# main_board.net
KiCad netlist of a schematic drawn in EAGLE
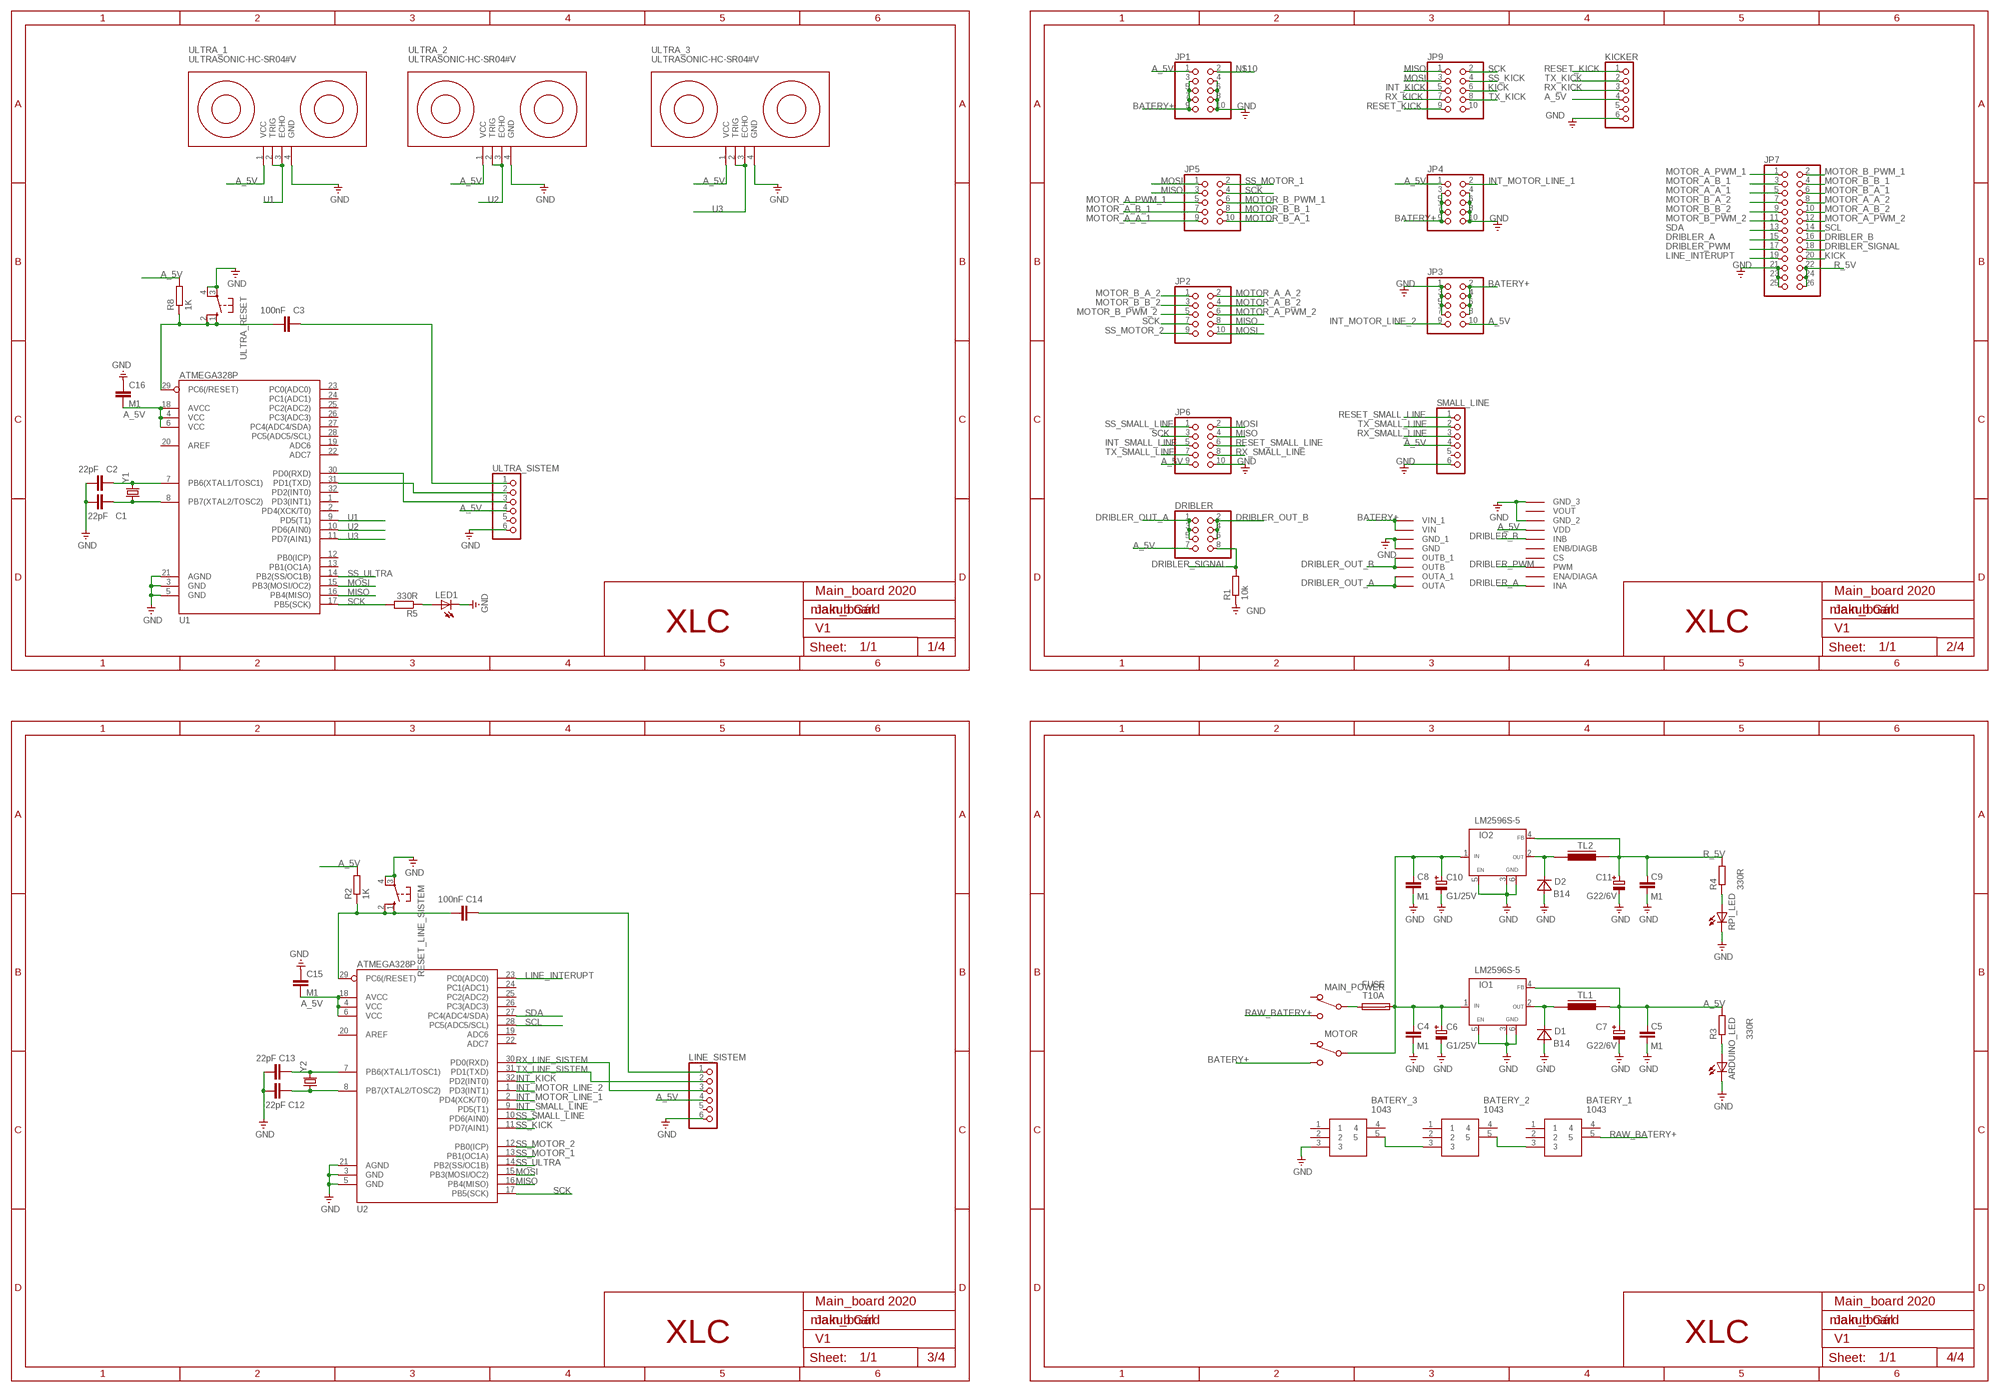
[diagram p0: schematic, sheet 1]

(export (version "E")
  (design (tool "Eeschema 10.0.6"))
  (components
    (comp (ref "ARDUINO_LED")
      (value "LEDCHIPLED_0603")
      (footprint "eagle-import:CHIPLED_0603")
      (libsource (lib "eagle-import") (part "LEDCHIPLED_0603"))
    )
    (comp (ref "BATERY_1")
      (value "1043")
      (footprint "eagle-import:1043")
      (fields (field (name "MOUSER_PART_NUMBER") "534-1043"))
      (libsource (lib "eagle-import") (part "1043"))
    )
    (comp (ref "BATERY_2")
      (value "1043")
      (footprint "eagle-import:1043")
      (fields (field (name "MOUSER_PART_NUMBER") "534-1043"))
      (libsource (lib "eagle-import") (part "1043"))
    )
    (comp (ref "BATERY_3")
      (value "1043")
      (footprint "eagle-import:1043")
      (fields (field (name "MOUSER_PART_NUMBER") "534-1043"))
      (libsource (lib "eagle-import") (part "1043"))
    )
    (comp (ref "C1")
      (value "22pF")
      (footprint "eagle-import:C0603")
      (libsource (lib "eagle-import") (part "C-EUC0603"))
    )
    (comp (ref "C2")
      (value "22pF")
      (footprint "eagle-import:C0603")
      (libsource (lib "eagle-import") (part "C-EUC0603"))
    )
    (comp (ref "C3")
      (value "100nF")
      (footprint "eagle-import:C0603")
      (libsource (lib "eagle-import") (part "C-EUC0603"))
    )
    (comp (ref "C4")
      (value "M1")
      (footprint "eagle-import:SMD-1206")
      (libsource (lib "eagle-import") (part "KOND-KERAM1206-SMD"))
    )
    (comp (ref "C5")
      (value "M1")
      (footprint "eagle-import:SMD-1206")
      (libsource (lib "eagle-import") (part "KOND-KERAM1206-SMD"))
    )
    (comp (ref "C6")
      (value "G1/25V")
      (footprint "eagle-import:SMD-ELE-D")
      (libsource (lib "eagle-import") (part "KOND-ELEKTD-SMD"))
    )
    (comp (ref "C7")
      (value "G22/6V")
      (footprint "eagle-import:SMD-ELE-D")
      (libsource (lib "eagle-import") (part "KOND-ELEKTD-SMD"))
    )
    (comp (ref "C8")
      (value "M1")
      (footprint "eagle-import:SMD-1206")
      (libsource (lib "eagle-import") (part "KOND-KERAM1206-SMD"))
    )
    (comp (ref "C9")
      (value "M1")
      (footprint "eagle-import:SMD-1206")
      (libsource (lib "eagle-import") (part "KOND-KERAM1206-SMD"))
    )
    (comp (ref "C10")
      (value "G1/25V")
      (footprint "eagle-import:SMD-ELE-D")
      (libsource (lib "eagle-import") (part "KOND-ELEKTD-SMD"))
    )
    (comp (ref "C11")
      (value "G22/6V")
      (footprint "eagle-import:SMD-ELE-D")
      (libsource (lib "eagle-import") (part "KOND-ELEKTD-SMD"))
    )
    (comp (ref "C12")
      (value "22pF")
      (footprint "eagle-import:C0603")
      (libsource (lib "eagle-import") (part "C-EUC0603"))
    )
    (comp (ref "C13")
      (value "22pF")
      (footprint "eagle-import:C0603")
      (libsource (lib "eagle-import") (part "C-EUC0603"))
    )
    (comp (ref "C14")
      (value "100nF")
      (footprint "eagle-import:C0603")
      (libsource (lib "eagle-import") (part "C-EUC0603"))
    )
    (comp (ref "C15")
      (value "M1")
      (footprint "eagle-import:C0603")
      (libsource (lib "eagle-import") (part "rcl_334_C-EUC0603"))
    )
    (comp (ref "C16")
      (value "M1")
      (footprint "eagle-import:C0603")
      (libsource (lib "eagle-import") (part "rcl_334_C-EUC0603"))
    )
    (comp (ref "D1")
      (value "B14")
      (footprint "eagle-import:D-3,6X5,5")
      (libsource (lib "eagle-import") (part "DIODASMD-3,6X5,5"))
    )
    (comp (ref "D2")
      (value "B14")
      (footprint "eagle-import:D-3,6X5,5")
      (libsource (lib "eagle-import") (part "DIODASMD-3,6X5,5"))
    )
    (comp (ref "DRIBLER")
      (value "PINHD-2X4_2.54-SMD")
      (footprint "eagle-import:2X04SMD")
      (libsource (lib "eagle-import") (part "PINHD-2X4_2.54-SMD"))
    )
    (comp (ref "FUSE")
      (value "T10A")
      (footprint "eagle-import:SH22,5A")
      (libsource (lib "eagle-import") (part "POISTKA2A"))
    )
    (comp (ref "IO1")
      (value "LM2596S-5")
      (footprint "eagle-import:TO263-5")
      (libsource (lib "eagle-import") (part "LM2596S"))
    )
    (comp (ref "IO2")
      (value "LM2596S-5")
      (footprint "eagle-import:TO263-5")
      (libsource (lib "eagle-import") (part "LM2596S"))
    )
    (comp (ref "JP1")
      (value "PINHD-2X5IDC")
      (footprint "eagle-import:2X05_IDC")
      (libsource (lib "eagle-import") (part "PINHD-2X5IDC"))
    )
    (comp (ref "JP2")
      (value "PINHD-2X5IDC")
      (footprint "eagle-import:2X05_IDC")
      (libsource (lib "eagle-import") (part "PINHD-2X5IDC"))
    )
    (comp (ref "JP3")
      (value "PINHD-2X5IDC")
      (footprint "eagle-import:2X05_IDC")
      (libsource (lib "eagle-import") (part "PINHD-2X5IDC"))
    )
    (comp (ref "JP4")
      (value "PINHD-2X5IDC")
      (footprint "eagle-import:2X05_IDC")
      (libsource (lib "eagle-import") (part "PINHD-2X5IDC"))
    )
    (comp (ref "JP5")
      (value "PINHD-2X5IDC")
      (footprint "eagle-import:2X05_IDC")
      (libsource (lib "eagle-import") (part "PINHD-2X5IDC"))
    )
    (comp (ref "JP6")
      (value "PINHD-2X5IDC")
      (footprint "eagle-import:2X05_IDC")
      (libsource (lib "eagle-import") (part "PINHD-2X5IDC"))
    )
    (comp (ref "JP7")
      (value "PINHD-2X13_2.54")
      (footprint "eagle-import:2X13")
      (libsource (lib "eagle-import") (part "PINHD-2X13_2.54"))
    )
    (comp (ref "JP9")
      (value "PINHD-2X5IDC")
      (footprint "eagle-import:2X05_IDC")
      (libsource (lib "eagle-import") (part "PINHD-2X5IDC"))
    )
    (comp (ref "KICKER")
      (value "PINHD-1X6")
      (footprint "eagle-import:1X06")
      (libsource (lib "eagle-import") (part "PINHD-1X6"))
    )
    (comp (ref "LED1")
      (value "LEDCHIPLED_0603")
      (footprint "eagle-import:CHIPLED_0603")
      (libsource (lib "eagle-import") (part "LEDCHIPLED_0603"))
    )
    (comp (ref "LINE_SISTEM")
      (value "PINHD-1X6")
      (footprint "eagle-import:1X06")
      (libsource (lib "eagle-import") (part "PINHD-1X6"))
    )
    (comp (ref "MAIN_POWER")
      (value "PREP-1PB")
      (footprint "eagle-import:P-B069B")
      (libsource (lib "eagle-import") (part "PREP-1PB"))
    )
    (comp (ref "MOTOR")
      (value "PREP-1PB")
      (footprint "eagle-import:P-B069B")
      (libsource (lib "eagle-import") (part "PREP-1PB"))
    )
    (comp (ref "R1")
      (value "10k")
      (footprint "eagle-import:R0603")
      (libsource (lib "eagle-import") (part "R-EU_R0603"))
    )
    (comp (ref "R2")
      (value "1K")
      (footprint "eagle-import:R0603")
      (libsource (lib "eagle-import") (part "R-EU_R0603"))
    )
    (comp (ref "R3")
      (value "330R")
      (footprint "eagle-import:R0603")
      (libsource (lib "eagle-import") (part "R-EU_R0603"))
    )
    (comp (ref "R4")
      (value "330R")
      (footprint "eagle-import:R0603")
      (libsource (lib "eagle-import") (part "R-EU_R0603"))
    )
    (comp (ref "R5")
      (value "330R")
      (footprint "eagle-import:R0603")
      (libsource (lib "eagle-import") (part "R-EU_R0603"))
    )
    (comp (ref "R8")
      (value "1K")
      (footprint "eagle-import:R0603")
      (libsource (lib "eagle-import") (part "R-EU_R0603"))
    )
    (comp (ref "RESET_LINE_SISTEM")
      (value "10-XX")
      (footprint "eagle-import:B3F-10XX")
      (fields (field (name "MPN") "B3F-1000"))
      (libsource (lib "eagle-import") (part "10-XX"))
    )
    (comp (ref "RPI_LED")
      (value "LEDCHIPLED_0603")
      (footprint "eagle-import:CHIPLED_0603")
      (libsource (lib "eagle-import") (part "LEDCHIPLED_0603"))
    )
    (comp (ref "SMALL_LINE")
      (value "PINHD-1X6")
      (footprint "eagle-import:1X06")
      (libsource (lib "eagle-import") (part "PINHD-1X6"))
    )
    (comp (ref "TL1")
      (value "INDUK-TLSMD1")
      (footprint "eagle-import:INDUK-TL")
      (libsource (lib "eagle-import") (part "INDUK-TLSMD1"))
    )
    (comp (ref "TL2")
      (value "INDUK-TLSMD1")
      (footprint "eagle-import:INDUK-TL")
      (libsource (lib "eagle-import") (part "INDUK-TLSMD1"))
    )
    (comp (ref "U$4")
      (value "MOTOR_DRIVER")
      (footprint "eagle-import:MOTOR_DRIVER")
      (libsource (lib "eagle-import") (part "MOTOR_DRIVER"))
    )
    (comp (ref "U1")
      (value "ATMEGA328P")
      (footprint "eagle-import:TQFP32-08")
      (libsource (lib "eagle-import") (part "ATMEGA328_SMT"))
    )
    (comp (ref "U2")
      (value "ATMEGA328P")
      (footprint "eagle-import:TQFP32-08")
      (libsource (lib "eagle-import") (part "ATMEGA328_SMT"))
    )
    (comp (ref "ULTRA_1")
      (value "ULTRASONIC-HC-SR04#V")
      (footprint "eagle-import:ULTRASONIC-HC-SR04#V")
      (libsource (lib "eagle-import") (part "ULTRASONIC-HC-SR04#V"))
    )
    (comp (ref "ULTRA_2")
      (value "ULTRASONIC-HC-SR04#V")
      (footprint "eagle-import:ULTRASONIC-HC-SR04#V")
      (libsource (lib "eagle-import") (part "ULTRASONIC-HC-SR04#V"))
    )
    (comp (ref "ULTRA_3")
      (value "ULTRASONIC-HC-SR04#V")
      (footprint "eagle-import:ULTRASONIC-HC-SR04#V")
      (libsource (lib "eagle-import") (part "ULTRASONIC-HC-SR04#V"))
    )
    (comp (ref "ULTRA_RESET")
      (value "10-XX")
      (footprint "eagle-import:B3F-10XX")
      (fields (field (name "MPN") "B3F-1000"))
      (libsource (lib "eagle-import") (part "10-XX"))
    )
    (comp (ref "ULTRA_SISTEM")
      (value "PINHD-1X6")
      (footprint "eagle-import:1X06")
      (libsource (lib "eagle-import") (part "PINHD-1X6"))
    )
    (comp (ref "Y1")
      (value "CRYSTALHC49US")
      (footprint "eagle-import:HC49US")
      (libsource (lib "eagle-import") (part "CRYSTALHC49US"))
    )
    (comp (ref "Y2")
      (value "CRYSTALHC49US")
      (footprint "eagle-import:HC49US")
      (libsource (lib "eagle-import") (part "CRYSTALHC49US"))
    )
  )
  (nets
    (net (code "1") (name "/A_5V") (class "Default")
      (node (ref "C15") (pin "2") (pinfunction "2_2") (pintype "passive"))
      (node (ref "C16") (pin "2") (pinfunction "2_2") (pintype "passive"))
      (node (ref "C5") (pin "2") (pinfunction "2_2") (pintype "passive"))
      (node (ref "C7") (pin "PLUS") (pinfunction "PLUS_PLUS") (pintype "passive"))
      (node (ref "DRIBLER") (pin "7") (pinfunction "7_7") (pintype "passive"))
      (node (ref "IO1") (pin "4") (pinfunction "FB_4") (pintype "input"))
      (node (ref "JP1") (pin "1") (pinfunction "1_1") (pintype "passive"))
      (node (ref "JP3") (pin "10") (pinfunction "10_10") (pintype "passive"))
      (node (ref "JP4") (pin "1") (pinfunction "1_1") (pintype "passive"))
      (node (ref "JP6") (pin "9") (pinfunction "9_9") (pintype "passive"))
      (node (ref "KICKER") (pin "4") (pinfunction "4_4") (pintype "passive"))
      (node (ref "LINE_SISTEM") (pin "4") (pinfunction "4_4") (pintype "passive"))
      (node (ref "R2") (pin "2") (pinfunction "2_2") (pintype "passive"))
      (node (ref "R3") (pin "2") (pinfunction "2_2") (pintype "passive"))
      (node (ref "R8") (pin "2") (pinfunction "2_2") (pintype "passive"))
      (node (ref "SMALL_LINE") (pin "4") (pinfunction "4_4") (pintype "passive"))
      (node (ref "TL1") (pin "2") (pinfunction "2_2") (pintype "passive"))
      (node (ref "U$4") (pin "VDD") (pinfunction "VDD_VDD") (pintype "bidirectional"))
      (node (ref "U1") (pin "18") (pinfunction "AVCC_18") (pintype "bidirectional"))
      (node (ref "U1") (pin "4") (pinfunction "VCC_4") (pintype "bidirectional"))
      (node (ref "U1") (pin "6") (pinfunction "VCC_6") (pintype "bidirectional"))
      (node (ref "U2") (pin "18") (pinfunction "AVCC_18") (pintype "bidirectional"))
      (node (ref "U2") (pin "4") (pinfunction "VCC_4") (pintype "bidirectional"))
      (node (ref "U2") (pin "6") (pinfunction "VCC_6") (pintype "bidirectional"))
      (node (ref "ULTRA_1") (pin "1") (pinfunction "VCC_1") (pintype "power_in"))
      (node (ref "ULTRA_2") (pin "1") (pinfunction "VCC_1") (pintype "power_in"))
      (node (ref "ULTRA_3") (pin "1") (pinfunction "VCC_1") (pintype "power_in"))
      (node (ref "ULTRA_SISTEM") (pin "4") (pinfunction "4_4") (pintype "passive"))
    )
    (net (code "2") (name "/BATERY+") (class "Default")
      (node (ref "JP1") (pin "3") (pinfunction "3_3") (pintype "passive"))
      (node (ref "JP1") (pin "5") (pinfunction "5_5") (pintype "passive"))
      (node (ref "JP1") (pin "7") (pinfunction "7_7") (pintype "passive"))
      (node (ref "JP1") (pin "9") (pinfunction "9_9") (pintype "passive"))
      (node (ref "JP3") (pin "2") (pinfunction "2_2") (pintype "passive"))
      (node (ref "JP3") (pin "4") (pinfunction "4_4") (pintype "passive"))
      (node (ref "JP3") (pin "6") (pinfunction "6_6") (pintype "passive"))
      (node (ref "JP3") (pin "8") (pinfunction "8_8") (pintype "passive"))
      (node (ref "JP4") (pin "3") (pinfunction "3_3") (pintype "passive"))
      (node (ref "JP4") (pin "5") (pinfunction "5_5") (pintype "passive"))
      (node (ref "JP4") (pin "7") (pinfunction "7_7") (pintype "passive"))
      (node (ref "JP4") (pin "9") (pinfunction "9_9") (pintype "passive"))
      (node (ref "MOTOR") (pin "1") (pinfunction "1-OFF_1") (pintype "passive"))
      (node (ref "U$4") (pin "VIN") (pinfunction "VIN_VIN") (pintype "bidirectional"))
      (node (ref "U$4") (pin "VIN_1") (pinfunction "VIN_1_VIN_1") (pintype "bidirectional"))
    )
    (net (code "3") (name "/DRIBLER_A") (class "Default")
      (node (ref "JP7") (pin "15") (pinfunction "15_15") (pintype "passive"))
      (node (ref "U$4") (pin "INA") (pinfunction "INA_INA") (pintype "bidirectional"))
    )
    (net (code "4") (name "/DRIBLER_B") (class "Default")
      (node (ref "JP7") (pin "16") (pinfunction "16_16") (pintype "passive"))
      (node (ref "U$4") (pin "INB") (pinfunction "INB_INB") (pintype "bidirectional"))
    )
    (net (code "5") (name "/DRIBLER_OUT_A") (class "Default")
      (node (ref "DRIBLER") (pin "1") (pinfunction "1_1") (pintype "passive"))
      (node (ref "DRIBLER") (pin "3") (pinfunction "3_3") (pintype "passive"))
      (node (ref "DRIBLER") (pin "5") (pinfunction "5_5") (pintype "passive"))
      (node (ref "U$4") (pin "OUTA") (pinfunction "OUTA_OUTA") (pintype "bidirectional"))
      (node (ref "U$4") (pin "OUTA_1") (pinfunction "OUTA_1_OUTA_1") (pintype "bidirectional"))
    )
    (net (code "6") (name "/DRIBLER_OUT_B") (class "Default")
      (node (ref "DRIBLER") (pin "2") (pinfunction "2_2") (pintype "passive"))
      (node (ref "DRIBLER") (pin "4") (pinfunction "4_4") (pintype "passive"))
      (node (ref "DRIBLER") (pin "6") (pinfunction "6_6") (pintype "passive"))
      (node (ref "U$4") (pin "OUTB") (pinfunction "OUTB_OUTB") (pintype "bidirectional"))
      (node (ref "U$4") (pin "OUTB_1") (pinfunction "OUTB_1_OUTB_1") (pintype "bidirectional"))
    )
    (net (code "7") (name "/DRIBLER_PWM") (class "Default")
      (node (ref "JP7") (pin "17") (pinfunction "17_17") (pintype "passive"))
      (node (ref "U$4") (pin "PWM") (pinfunction "PWM_PWM") (pintype "bidirectional"))
    )
    (net (code "8") (name "/DRIBLER_SIGNAL") (class "Default")
      (node (ref "DRIBLER") (pin "8") (pinfunction "8_8") (pintype "passive"))
      (node (ref "JP7") (pin "18") (pinfunction "18_18") (pintype "passive"))
      (node (ref "R1") (pin "2") (pinfunction "2_2") (pintype "passive"))
    )
    (net (code "9") (name "/INT_KICK") (class "Default")
      (node (ref "JP9") (pin "5") (pinfunction "5_5") (pintype "passive"))
      (node (ref "U2") (pin "32") (pinfunction "PD2(INT0)_32") (pintype "bidirectional"))
    )
    (net (code "10") (name "/INT_MOTOR_LINE_1") (class "Default")
      (node (ref "JP4") (pin "2") (pinfunction "2_2") (pintype "passive"))
      (node (ref "U2") (pin "2") (pinfunction "PD4(XCK/T0)_2") (pintype "bidirectional"))
    )
    (net (code "11") (name "/INT_MOTOR_LINE_2") (class "Default")
      (node (ref "JP3") (pin "9") (pinfunction "9_9") (pintype "passive"))
      (node (ref "U2") (pin "1") (pinfunction "PD3(INT1)_1") (pintype "bidirectional"))
    )
    (net (code "12") (name "/INT_SMALL_LINE") (class "Default")
      (node (ref "JP6") (pin "5") (pinfunction "5_5") (pintype "passive"))
      (node (ref "U2") (pin "9") (pinfunction "PD5(T1)_9") (pintype "bidirectional"))
    )
    (net (code "13") (name "/KICK") (class "Default")
      (node (ref "JP7") (pin "20") (pinfunction "20_20") (pintype "passive"))
      (node (ref "JP9") (pin "6") (pinfunction "6_6") (pintype "passive"))
    )
    (net (code "14") (name "/LINE_INTERUPT") (class "Default")
      (node (ref "JP7") (pin "19") (pinfunction "19_19") (pintype "passive"))
      (node (ref "U2") (pin "23") (pinfunction "PC0(ADC0)_23") (pintype "bidirectional"))
    )
    (net (code "15") (name "/MISO") (class "Default")
      (node (ref "JP2") (pin "8") (pinfunction "8_8") (pintype "passive"))
      (node (ref "JP5") (pin "3") (pinfunction "3_3") (pintype "passive"))
      (node (ref "JP6") (pin "4") (pinfunction "4_4") (pintype "passive"))
      (node (ref "JP9") (pin "1") (pinfunction "1_1") (pintype "passive"))
      (node (ref "U1") (pin "16") (pinfunction "PB4(MISO)_16") (pintype "bidirectional"))
      (node (ref "U2") (pin "16") (pinfunction "PB4(MISO)_16") (pintype "bidirectional"))
    )
    (net (code "16") (name "/MOSI") (class "Default")
      (node (ref "JP2") (pin "10") (pinfunction "10_10") (pintype "passive"))
      (node (ref "JP5") (pin "1") (pinfunction "1_1") (pintype "passive"))
      (node (ref "JP6") (pin "2") (pinfunction "2_2") (pintype "passive"))
      (node (ref "JP9") (pin "3") (pinfunction "3_3") (pintype "passive"))
      (node (ref "U1") (pin "15") (pinfunction "PB3(MOSI/OC2)_15") (pintype "bidirectional"))
      (node (ref "U2") (pin "15") (pinfunction "PB3(MOSI/OC2)_15") (pintype "bidirectional"))
    )
    (net (code "17") (name "/MOTOR_A_A_1") (class "Default")
      (node (ref "JP5") (pin "9") (pinfunction "9_9") (pintype "passive"))
      (node (ref "JP7") (pin "5") (pinfunction "5_5") (pintype "passive"))
    )
    (net (code "18") (name "/MOTOR_A_A_2") (class "Default")
      (node (ref "JP2") (pin "2") (pinfunction "2_2") (pintype "passive"))
      (node (ref "JP7") (pin "8") (pinfunction "8_8") (pintype "passive"))
    )
    (net (code "19") (name "/MOTOR_A_B_1") (class "Default")
      (node (ref "JP5") (pin "7") (pinfunction "7_7") (pintype "passive"))
      (node (ref "JP7") (pin "3") (pinfunction "3_3") (pintype "passive"))
    )
    (net (code "20") (name "/MOTOR_A_B_2") (class "Default")
      (node (ref "JP2") (pin "4") (pinfunction "4_4") (pintype "passive"))
      (node (ref "JP7") (pin "10") (pinfunction "10_10") (pintype "passive"))
    )
    (net (code "21") (name "/MOTOR_A_PWM_1") (class "Default")
      (node (ref "JP5") (pin "5") (pinfunction "5_5") (pintype "passive"))
      (node (ref "JP7") (pin "1") (pinfunction "1_1") (pintype "passive"))
    )
    (net (code "22") (name "/MOTOR_A_PWM_2") (class "Default")
      (node (ref "JP2") (pin "6") (pinfunction "6_6") (pintype "passive"))
      (node (ref "JP7") (pin "12") (pinfunction "12_12") (pintype "passive"))
    )
    (net (code "23") (name "/MOTOR_B_A_1") (class "Default")
      (node (ref "JP5") (pin "10") (pinfunction "10_10") (pintype "passive"))
      (node (ref "JP7") (pin "6") (pinfunction "6_6") (pintype "passive"))
    )
    (net (code "24") (name "/MOTOR_B_A_2") (class "Default")
      (node (ref "JP2") (pin "1") (pinfunction "1_1") (pintype "passive"))
      (node (ref "JP7") (pin "7") (pinfunction "7_7") (pintype "passive"))
    )
    (net (code "25") (name "/MOTOR_B_B_1") (class "Default")
      (node (ref "JP5") (pin "8") (pinfunction "8_8") (pintype "passive"))
      (node (ref "JP7") (pin "4") (pinfunction "4_4") (pintype "passive"))
    )
    (net (code "26") (name "/MOTOR_B_B_2") (class "Default")
      (node (ref "JP2") (pin "3") (pinfunction "3_3") (pintype "passive"))
      (node (ref "JP7") (pin "9") (pinfunction "9_9") (pintype "passive"))
    )
    (net (code "27") (name "/MOTOR_B_PWM_1") (class "Default")
      (node (ref "JP5") (pin "6") (pinfunction "6_6") (pintype "passive"))
      (node (ref "JP7") (pin "2") (pinfunction "2_2") (pintype "passive"))
    )
    (net (code "28") (name "/MOTOR_B_PWM_2") (class "Default")
      (node (ref "JP2") (pin "5") (pinfunction "5_5") (pintype "passive"))
      (node (ref "JP7") (pin "11") (pinfunction "11_11") (pintype "passive"))
    )
    (net (code "29") (name "/N$10") (class "Default")
      (node (ref "JP1") (pin "2") (pinfunction "2_2") (pintype "passive"))
    )
    (net (code "30") (name "/RAW_BATERY+") (class "Default")
      (node (ref "BATERY_1") (pin "5") (pinfunction "5_5") (pintype "bidirectional"))
      (node (ref "MAIN_POWER") (pin "1") (pinfunction "1-OFF_1") (pintype "passive"))
    )
    (net (code "31") (name "/RESET_KICK") (class "Default")
      (node (ref "JP9") (pin "9") (pinfunction "9_9") (pintype "passive"))
      (node (ref "KICKER") (pin "1") (pinfunction "1_1") (pintype "passive"))
    )
    (net (code "32") (name "/RESET_SMALL_LINE") (class "Default")
      (node (ref "JP6") (pin "6") (pinfunction "6_6") (pintype "passive"))
      (node (ref "SMALL_LINE") (pin "1") (pinfunction "1_1") (pintype "passive"))
    )
    (net (code "33") (name "/RX_KICK") (class "Default")
      (node (ref "JP9") (pin "7") (pinfunction "7_7") (pintype "passive"))
      (node (ref "KICKER") (pin "3") (pinfunction "3_3") (pintype "passive"))
    )
    (net (code "34") (name "/RX_LINE_SISTEM") (class "Default")
      (node (ref "LINE_SISTEM") (pin "3") (pinfunction "3_3") (pintype "passive"))
      (node (ref "U2") (pin "30") (pinfunction "PD0(RXD)_30") (pintype "bidirectional"))
    )
    (net (code "35") (name "/RX_SMALL_LINE") (class "Default")
      (node (ref "JP6") (pin "8") (pinfunction "8_8") (pintype "passive"))
      (node (ref "SMALL_LINE") (pin "3") (pinfunction "3_3") (pintype "passive"))
    )
    (net (code "36") (name "/R_5V") (class "Default")
      (node (ref "C11") (pin "PLUS") (pinfunction "PLUS_PLUS") (pintype "passive"))
      (node (ref "C9") (pin "2") (pinfunction "2_2") (pintype "passive"))
      (node (ref "IO2") (pin "4") (pinfunction "FB_4") (pintype "input"))
      (node (ref "JP7") (pin "22") (pinfunction "22_22") (pintype "passive"))
      (node (ref "JP7") (pin "24") (pinfunction "24_24") (pintype "passive"))
      (node (ref "JP7") (pin "26") (pinfunction "26_26") (pintype "passive"))
      (node (ref "R4") (pin "2") (pinfunction "2_2") (pintype "passive"))
      (node (ref "TL2") (pin "2") (pinfunction "2_2") (pintype "passive"))
    )
    (net (code "37") (name "/SCK") (class "Default")
      (node (ref "JP2") (pin "7") (pinfunction "7_7") (pintype "passive"))
      (node (ref "JP5") (pin "4") (pinfunction "4_4") (pintype "passive"))
      (node (ref "JP6") (pin "3") (pinfunction "3_3") (pintype "passive"))
      (node (ref "JP9") (pin "2") (pinfunction "2_2") (pintype "passive"))
      (node (ref "R5") (pin "2") (pinfunction "2_2") (pintype "passive"))
      (node (ref "U1") (pin "17") (pinfunction "PB5(SCK)_17") (pintype "bidirectional"))
      (node (ref "U2") (pin "17") (pinfunction "PB5(SCK)_17") (pintype "bidirectional"))
    )
    (net (code "38") (name "/SCL") (class "Default")
      (node (ref "JP7") (pin "14") (pinfunction "14_14") (pintype "passive"))
      (node (ref "U2") (pin "28") (pinfunction "PC5(ADC5/SCL)_28") (pintype "bidirectional"))
    )
    (net (code "39") (name "/SDA") (class "Default")
      (node (ref "JP7") (pin "13") (pinfunction "13_13") (pintype "passive"))
      (node (ref "U2") (pin "27") (pinfunction "PC4(ADC4/SDA)_27") (pintype "bidirectional"))
    )
    (net (code "40") (name "/SS_KICK") (class "Default")
      (node (ref "JP9") (pin "4") (pinfunction "4_4") (pintype "passive"))
      (node (ref "U2") (pin "11") (pinfunction "PD7(AIN1)_11") (pintype "bidirectional"))
    )
    (net (code "41") (name "/SS_MOTOR_1") (class "Default")
      (node (ref "JP5") (pin "2") (pinfunction "2_2") (pintype "passive"))
      (node (ref "U2") (pin "13") (pinfunction "PB1(OC1A)_13") (pintype "bidirectional"))
    )
    (net (code "42") (name "/SS_MOTOR_2") (class "Default")
      (node (ref "JP2") (pin "9") (pinfunction "9_9") (pintype "passive"))
      (node (ref "U2") (pin "12") (pinfunction "PB0(ICP)_12") (pintype "bidirectional"))
    )
    (net (code "43") (name "/SS_SMALL_LINE") (class "Default")
      (node (ref "JP6") (pin "1") (pinfunction "1_1") (pintype "passive"))
      (node (ref "U2") (pin "10") (pinfunction "PD6(AIN0)_10") (pintype "bidirectional"))
    )
    (net (code "44") (name "/SS_ULTRA") (class "Default")
      (node (ref "U1") (pin "14") (pinfunction "PB2(SS/OC1B)_14") (pintype "bidirectional"))
      (node (ref "U2") (pin "14") (pinfunction "PB2(SS/OC1B)_14") (pintype "bidirectional"))
    )
    (net (code "45") (name "/TX_KICK") (class "Default")
      (node (ref "JP9") (pin "8") (pinfunction "8_8") (pintype "passive"))
      (node (ref "KICKER") (pin "2") (pinfunction "2_2") (pintype "passive"))
    )
    (net (code "46") (name "/TX_LINE_SISTEM") (class "Default")
      (node (ref "LINE_SISTEM") (pin "2") (pinfunction "2_2") (pintype "passive"))
      (node (ref "U2") (pin "31") (pinfunction "PD1(TXD)_31") (pintype "bidirectional"))
    )
    (net (code "47") (name "/TX_SMALL_LINE") (class "Default")
      (node (ref "JP6") (pin "7") (pinfunction "7_7") (pintype "passive"))
      (node (ref "SMALL_LINE") (pin "2") (pinfunction "2_2") (pintype "passive"))
    )
    (net (code "48") (name "/U1") (class "Default")
      (node (ref "U1") (pin "9") (pinfunction "PD5(T1)_9") (pintype "bidirectional"))
      (node (ref "ULTRA_1") (pin "2") (pinfunction "TRIG_2") (pintype "input"))
      (node (ref "ULTRA_1") (pin "3") (pinfunction "ECHO_3") (pintype "output"))
    )
    (net (code "49") (name "/U2") (class "Default")
      (node (ref "U1") (pin "10") (pinfunction "PD6(AIN0)_10") (pintype "bidirectional"))
      (node (ref "ULTRA_2") (pin "2") (pinfunction "TRIG_2") (pintype "input"))
      (node (ref "ULTRA_2") (pin "3") (pinfunction "ECHO_3") (pintype "output"))
    )
    (net (code "50") (name "/U3") (class "Default")
      (node (ref "U1") (pin "11") (pinfunction "PD7(AIN1)_11") (pintype "bidirectional"))
      (node (ref "ULTRA_3") (pin "2") (pinfunction "TRIG_2") (pintype "input"))
      (node (ref "ULTRA_3") (pin "3") (pinfunction "ECHO_3") (pintype "output"))
    )
    (net (code "51") (name "GND") (class "Default")
      (node (ref "ARDUINO_LED") (pin "C") (pinfunction "C_C") (pintype "passive"))
      (node (ref "BATERY_3") (pin "3") (pinfunction "3_3") (pintype "bidirectional"))
      (node (ref "C1") (pin "1") (pinfunction "1_1") (pintype "passive"))
      (node (ref "C10") (pin "MINUS") (pinfunction "MINUS_MINUS") (pintype "passive"))
      (node (ref "C11") (pin "MINUS") (pinfunction "MINUS_MINUS") (pintype "passive"))
      (node (ref "C12") (pin "1") (pinfunction "1_1") (pintype "passive"))
      (node (ref "C13") (pin "1") (pinfunction "1_1") (pintype "passive"))
      (node (ref "C15") (pin "1") (pinfunction "1_1") (pintype "passive"))
      (node (ref "C16") (pin "1") (pinfunction "1_1") (pintype "passive"))
      (node (ref "C2") (pin "1") (pinfunction "1_1") (pintype "passive"))
      (node (ref "C4") (pin "1") (pinfunction "1_1") (pintype "passive"))
      (node (ref "C5") (pin "1") (pinfunction "1_1") (pintype "passive"))
      (node (ref "C6") (pin "MINUS") (pinfunction "MINUS_MINUS") (pintype "passive"))
      (node (ref "C7") (pin "MINUS") (pinfunction "MINUS_MINUS") (pintype "passive"))
      (node (ref "C8") (pin "1") (pinfunction "1_1") (pintype "passive"))
      (node (ref "C9") (pin "1") (pinfunction "1_1") (pintype "passive"))
      (node (ref "D1") (pin "A") (pinfunction "A_A") (pintype "passive"))
      (node (ref "D2") (pin "A") (pinfunction "A_A") (pintype "passive"))
      (node (ref "IO1") (pin "3") (pinfunction "GND_3") (pintype "power_in"))
      (node (ref "IO1") (pin "5") (pinfunction "EN_5") (pintype "input"))
      (node (ref "IO1") (pin "6") (pinfunction "GND_6") (pintype "power_in"))
      (node (ref "IO2") (pin "3") (pinfunction "GND_3") (pintype "power_in"))
      (node (ref "IO2") (pin "5") (pinfunction "EN_5") (pintype "input"))
      (node (ref "IO2") (pin "6") (pinfunction "GND_6") (pintype "power_in"))
      (node (ref "JP1") (pin "10") (pinfunction "10_10") (pintype "passive"))
      (node (ref "JP1") (pin "4") (pinfunction "4_4") (pintype "passive"))
      (node (ref "JP1") (pin "6") (pinfunction "6_6") (pintype "passive"))
      (node (ref "JP1") (pin "8") (pinfunction "8_8") (pintype "passive"))
      (node (ref "JP3") (pin "1") (pinfunction "1_1") (pintype "passive"))
      (node (ref "JP3") (pin "3") (pinfunction "3_3") (pintype "passive"))
      (node (ref "JP3") (pin "5") (pinfunction "5_5") (pintype "passive"))
      (node (ref "JP3") (pin "7") (pinfunction "7_7") (pintype "passive"))
      (node (ref "JP4") (pin "10") (pinfunction "10_10") (pintype "passive"))
      (node (ref "JP4") (pin "4") (pinfunction "4_4") (pintype "passive"))
      (node (ref "JP4") (pin "6") (pinfunction "6_6") (pintype "passive"))
      (node (ref "JP4") (pin "8") (pinfunction "8_8") (pintype "passive"))
      (node (ref "JP6") (pin "10") (pinfunction "10_10") (pintype "passive"))
      (node (ref "JP7") (pin "21") (pinfunction "21_21") (pintype "passive"))
      (node (ref "JP7") (pin "23") (pinfunction "23_23") (pintype "passive"))
      (node (ref "JP7") (pin "25") (pinfunction "25_25") (pintype "passive"))
      (node (ref "KICKER") (pin "6") (pinfunction "6_6") (pintype "passive"))
      (node (ref "LED1") (pin "C") (pinfunction "C_C") (pintype "passive"))
      (node (ref "LINE_SISTEM") (pin "6") (pinfunction "6_6") (pintype "passive"))
      (node (ref "R1") (pin "1") (pinfunction "1_1") (pintype "passive"))
      (node (ref "RESET_LINE_SISTEM") (pin "3") (pinfunction "P_3") (pintype "passive"))
      (node (ref "RESET_LINE_SISTEM") (pin "4") (pinfunction "P1_4") (pintype "passive"))
      (node (ref "RPI_LED") (pin "C") (pinfunction "C_C") (pintype "passive"))
      (node (ref "SMALL_LINE") (pin "6") (pinfunction "6_6") (pintype "passive"))
      (node (ref "U$4") (pin "GND") (pinfunction "GND_GND") (pintype "bidirectional"))
      (node (ref "U$4") (pin "GND_1") (pinfunction "GND_1_GND_1") (pintype "bidirectional"))
      (node (ref "U$4") (pin "GND_2") (pinfunction "GND_2_GND_2") (pintype "bidirectional"))
      (node (ref "U$4") (pin "GND_3") (pinfunction "GND_3_GND_3") (pintype "bidirectional"))
      (node (ref "U1") (pin "21") (pinfunction "AGND_21") (pintype "bidirectional"))
      (node (ref "U1") (pin "3") (pinfunction "GND_3") (pintype "bidirectional"))
      (node (ref "U1") (pin "5") (pinfunction "GND_5") (pintype "bidirectional"))
      (node (ref "U2") (pin "21") (pinfunction "AGND_21") (pintype "bidirectional"))
      (node (ref "U2") (pin "3") (pinfunction "GND_3") (pintype "bidirectional"))
      (node (ref "U2") (pin "5") (pinfunction "GND_5") (pintype "bidirectional"))
      (node (ref "ULTRA_1") (pin "4") (pinfunction "GND_4") (pintype "power_in"))
      (node (ref "ULTRA_2") (pin "4") (pinfunction "GND_4") (pintype "power_in"))
      (node (ref "ULTRA_3") (pin "4") (pinfunction "GND_4") (pintype "power_in"))
      (node (ref "ULTRA_RESET") (pin "3") (pinfunction "P_3") (pintype "passive"))
      (node (ref "ULTRA_RESET") (pin "4") (pinfunction "P1_4") (pintype "passive"))
      (node (ref "ULTRA_SISTEM") (pin "6") (pinfunction "6_6") (pintype "passive"))
    )
    (net (code "52") (name "Net-(ARDUINO_LED-PadA)") (class "Default")
      (node (ref "ARDUINO_LED") (pin "A") (pinfunction "A_A") (pintype "passive"))
      (node (ref "R3") (pin "1") (pinfunction "1_1") (pintype "passive"))
    )
    (net (code "53") (name "Net-(BATERY_1-Pad3)") (class "Default")
      (node (ref "BATERY_1") (pin "3") (pinfunction "3_3") (pintype "bidirectional"))
      (node (ref "BATERY_2") (pin "5") (pinfunction "5_5") (pintype "bidirectional"))
    )
    (net (code "54") (name "Net-(BATERY_2-Pad3)") (class "Default")
      (node (ref "BATERY_2") (pin "3") (pinfunction "3_3") (pintype "bidirectional"))
      (node (ref "BATERY_3") (pin "5") (pinfunction "5_5") (pintype "bidirectional"))
    )
    (net (code "55") (name "Net-(C3-Pad2)") (class "Default")
      (node (ref "C3") (pin "2") (pinfunction "2_2") (pintype "passive"))
      (node (ref "ULTRA_SISTEM") (pin "1") (pinfunction "1_1") (pintype "passive"))
    )
    (net (code "56") (name "Net-(C14-Pad2)") (class "Default")
      (node (ref "C14") (pin "2") (pinfunction "2_2") (pintype "passive"))
      (node (ref "LINE_SISTEM") (pin "1") (pinfunction "1_1") (pintype "passive"))
    )
    (net (code "57") (name "Net-(IO1-IN)") (class "Default")
      (node (ref "C10") (pin "PLUS") (pinfunction "PLUS_PLUS") (pintype "passive"))
      (node (ref "C4") (pin "2") (pinfunction "2_2") (pintype "passive"))
      (node (ref "C6") (pin "PLUS") (pinfunction "PLUS_PLUS") (pintype "passive"))
      (node (ref "C8") (pin "2") (pinfunction "2_2") (pintype "passive"))
      (node (ref "FUSE") (pin "2") (pinfunction "2_2") (pintype "passive"))
      (node (ref "IO1") (pin "1") (pinfunction "IN_1") (pintype "input"))
      (node (ref "IO2") (pin "1") (pinfunction "IN_1") (pintype "input"))
      (node (ref "MOTOR") (pin "2") (pinfunction "2-COM_2") (pintype "passive"))
    )
    (net (code "58") (name "Net-(IO1-OUT)") (class "Default")
      (node (ref "D1") (pin "K") (pinfunction "K_K") (pintype "passive"))
      (node (ref "IO1") (pin "2") (pinfunction "OUT_2") (pintype "output"))
      (node (ref "TL1") (pin "1") (pinfunction "1_1") (pintype "passive"))
    )
    (net (code "59") (name "Net-(IO2-OUT)") (class "Default")
      (node (ref "D2") (pin "K") (pinfunction "K_K") (pintype "passive"))
      (node (ref "IO2") (pin "2") (pinfunction "OUT_2") (pintype "output"))
      (node (ref "TL2") (pin "1") (pinfunction "1_1") (pintype "passive"))
    )
    (net (code "60") (name "Net-(LED1-PadA)") (class "Default")
      (node (ref "LED1") (pin "A") (pinfunction "A_A") (pintype "passive"))
      (node (ref "R5") (pin "1") (pinfunction "1_1") (pintype "passive"))
    )
    (net (code "61") (name "Net-(MAIN_POWER-2-COM)") (class "Default")
      (node (ref "FUSE") (pin "1") (pinfunction "1_1") (pintype "passive"))
      (node (ref "MAIN_POWER") (pin "2") (pinfunction "2-COM_2") (pintype "passive"))
    )
    (net (code "62") (name "Net-(R4-Pad1)") (class "Default")
      (node (ref "R4") (pin "1") (pinfunction "1_1") (pintype "passive"))
      (node (ref "RPI_LED") (pin "A") (pinfunction "A_A") (pintype "passive"))
    )
    (net (code "63") (name "Net-(RESET_LINE_SISTEM-S)") (class "Default")
      (node (ref "C14") (pin "1") (pinfunction "1_1") (pintype "passive"))
      (node (ref "R2") (pin "1") (pinfunction "1_1") (pintype "passive"))
      (node (ref "RESET_LINE_SISTEM") (pin "1") (pinfunction "S_1") (pintype "passive"))
      (node (ref "RESET_LINE_SISTEM") (pin "2") (pinfunction "S1_2") (pintype "passive"))
      (node (ref "U2") (pin "29") (pinfunction "PC6(/RESET)_29") (pintype "bidirectional"))
    )
    (net (code "64") (name "Net-(U1-PB6(XTAL1{slash}TOSC1))") (class "Default")
      (node (ref "C2") (pin "2") (pinfunction "2_2") (pintype "passive"))
      (node (ref "U1") (pin "7") (pinfunction "PB6(XTAL1/TOSC1)_7") (pintype "bidirectional"))
      (node (ref "Y1") (pin "2") (pinfunction "2_2") (pintype "passive"))
    )
    (net (code "65") (name "Net-(U1-PB7(XTAL2{slash}TOSC2))") (class "Default")
      (node (ref "C1") (pin "2") (pinfunction "2_2") (pintype "passive"))
      (node (ref "U1") (pin "8") (pinfunction "PB7(XTAL2/TOSC2)_8") (pintype "bidirectional"))
      (node (ref "Y1") (pin "1") (pinfunction "1_1") (pintype "passive"))
    )
    (net (code "66") (name "Net-(U1-PC6({slash}RESET))") (class "Default")
      (node (ref "C3") (pin "1") (pinfunction "1_1") (pintype "passive"))
      (node (ref "R8") (pin "1") (pinfunction "1_1") (pintype "passive"))
      (node (ref "U1") (pin "29") (pinfunction "PC6(/RESET)_29") (pintype "bidirectional"))
      (node (ref "ULTRA_RESET") (pin "1") (pinfunction "S_1") (pintype "passive"))
      (node (ref "ULTRA_RESET") (pin "2") (pinfunction "S1_2") (pintype "passive"))
    )
    (net (code "67") (name "Net-(U1-PD0(RXD))") (class "Default")
      (node (ref "U1") (pin "30") (pinfunction "PD0(RXD)_30") (pintype "bidirectional"))
      (node (ref "ULTRA_SISTEM") (pin "3") (pinfunction "3_3") (pintype "passive"))
    )
    (net (code "68") (name "Net-(U1-PD1(TXD))") (class "Default")
      (node (ref "U1") (pin "31") (pinfunction "PD1(TXD)_31") (pintype "bidirectional"))
      (node (ref "ULTRA_SISTEM") (pin "2") (pinfunction "2_2") (pintype "passive"))
    )
    (net (code "69") (name "Net-(U2-PB6(XTAL1{slash}TOSC1))") (class "Default")
      (node (ref "C13") (pin "2") (pinfunction "2_2") (pintype "passive"))
      (node (ref "U2") (pin "7") (pinfunction "PB6(XTAL1/TOSC1)_7") (pintype "bidirectional"))
      (node (ref "Y2") (pin "2") (pinfunction "2_2") (pintype "passive"))
    )
    (net (code "70") (name "Net-(U2-PB7(XTAL2{slash}TOSC2))") (class "Default")
      (node (ref "C12") (pin "2") (pinfunction "2_2") (pintype "passive"))
      (node (ref "U2") (pin "8") (pinfunction "PB7(XTAL2/TOSC2)_8") (pintype "bidirectional"))
      (node (ref "Y2") (pin "1") (pinfunction "1_1") (pintype "passive"))
    )
    (net (code "71") (name "unconnected-(BATERY_1-Pad1)") (class "Default")
      (node (ref "BATERY_1") (pin "1") (pinfunction "1_1") (pintype "bidirectional"))
    )
    (net (code "72") (name "unconnected-(BATERY_1-Pad2)") (class "Default")
      (node (ref "BATERY_1") (pin "2") (pinfunction "2_2") (pintype "bidirectional"))
    )
    (net (code "73") (name "unconnected-(BATERY_1-Pad4)") (class "Default")
      (node (ref "BATERY_1") (pin "4") (pinfunction "4_4") (pintype "bidirectional"))
    )
    (net (code "74") (name "unconnected-(BATERY_2-Pad1)") (class "Default")
      (node (ref "BATERY_2") (pin "1") (pinfunction "1_1") (pintype "bidirectional"))
    )
    (net (code "75") (name "unconnected-(BATERY_2-Pad2)") (class "Default")
      (node (ref "BATERY_2") (pin "2") (pinfunction "2_2") (pintype "bidirectional"))
    )
    (net (code "76") (name "unconnected-(BATERY_2-Pad4)") (class "Default")
      (node (ref "BATERY_2") (pin "4") (pinfunction "4_4") (pintype "bidirectional"))
    )
    (net (code "77") (name "unconnected-(BATERY_3-Pad1)") (class "Default")
      (node (ref "BATERY_3") (pin "1") (pinfunction "1_1") (pintype "bidirectional"))
    )
    (net (code "78") (name "unconnected-(BATERY_3-Pad2)") (class "Default")
      (node (ref "BATERY_3") (pin "2") (pinfunction "2_2") (pintype "bidirectional"))
    )
    (net (code "79") (name "unconnected-(BATERY_3-Pad4)") (class "Default")
      (node (ref "BATERY_3") (pin "4") (pinfunction "4_4") (pintype "bidirectional"))
    )
    (net (code "80") (name "unconnected-(JP9-Pad10)") (class "Default")
      (node (ref "JP9") (pin "10") (pinfunction "10_10") (pintype "passive"))
    )
    (net (code "81") (name "unconnected-(KICKER-Pad5)") (class "Default")
      (node (ref "KICKER") (pin "5") (pinfunction "5_5") (pintype "passive"))
    )
    (net (code "82") (name "unconnected-(LINE_SISTEM-Pad5)") (class "Default")
      (node (ref "LINE_SISTEM") (pin "5") (pinfunction "5_5") (pintype "passive"))
    )
    (net (code "83") (name "unconnected-(MAIN_POWER-3-ON-Pad3)") (class "Default")
      (node (ref "MAIN_POWER") (pin "3") (pinfunction "3-ON_3") (pintype "passive"))
    )
    (net (code "84") (name "unconnected-(MOTOR-3-ON-Pad3)") (class "Default")
      (node (ref "MOTOR") (pin "3") (pinfunction "3-ON_3") (pintype "passive"))
    )
    (net (code "85") (name "unconnected-(SMALL_LINE-Pad5)") (class "Default")
      (node (ref "SMALL_LINE") (pin "5") (pinfunction "5_5") (pintype "passive"))
    )
    (net (code "86") (name "unconnected-(U$4-PadCS)") (class "Default")
      (node (ref "U$4") (pin "CS") (pinfunction "CS_CS") (pintype "bidirectional"))
    )
    (net (code "87") (name "unconnected-(U$4-PadENA{slash}DIAGA)") (class "Default")
      (node (ref "U$4") (pin "ENA/DIAGA") (pinfunction "ENA/DIAGA_ENA/DIAGA") (pintype "bidirectional"))
    )
    (net (code "88") (name "unconnected-(U$4-PadENB{slash}DIAGB)") (class "Default")
      (node (ref "U$4") (pin "ENB/DIAGB") (pinfunction "ENB/DIAGB_ENB/DIAGB") (pintype "bidirectional"))
    )
    (net (code "89") (name "unconnected-(U$4-PadVOUT)") (class "Default")
      (node (ref "U$4") (pin "VOUT") (pinfunction "VOUT_VOUT") (pintype "bidirectional"))
    )
    (net (code "90") (name "unconnected-(U1-ADC6-Pad19)") (class "Default")
      (node (ref "U1") (pin "19") (pinfunction "ADC6_19") (pintype "bidirectional"))
    )
    (net (code "91") (name "unconnected-(U1-ADC7-Pad22)") (class "Default")
      (node (ref "U1") (pin "22") (pinfunction "ADC7_22") (pintype "bidirectional"))
    )
    (net (code "92") (name "unconnected-(U1-AREF-Pad20)") (class "Default")
      (node (ref "U1") (pin "20") (pinfunction "AREF_20") (pintype "bidirectional"))
    )
    (net (code "93") (name "unconnected-(U1-PB0(ICP)-Pad12)") (class "Default")
      (node (ref "U1") (pin "12") (pinfunction "PB0(ICP)_12") (pintype "bidirectional"))
    )
    (net (code "94") (name "unconnected-(U1-PB1(OC1A)-Pad13)") (class "Default")
      (node (ref "U1") (pin "13") (pinfunction "PB1(OC1A)_13") (pintype "bidirectional"))
    )
    (net (code "95") (name "unconnected-(U1-PC0(ADC0)-Pad23)") (class "Default")
      (node (ref "U1") (pin "23") (pinfunction "PC0(ADC0)_23") (pintype "bidirectional"))
    )
    (net (code "96") (name "unconnected-(U1-PC1(ADC1)-Pad24)") (class "Default")
      (node (ref "U1") (pin "24") (pinfunction "PC1(ADC1)_24") (pintype "bidirectional"))
    )
    (net (code "97") (name "unconnected-(U1-PC2(ADC2)-Pad25)") (class "Default")
      (node (ref "U1") (pin "25") (pinfunction "PC2(ADC2)_25") (pintype "bidirectional"))
    )
    (net (code "98") (name "unconnected-(U1-PC3(ADC3)-Pad26)") (class "Default")
      (node (ref "U1") (pin "26") (pinfunction "PC3(ADC3)_26") (pintype "bidirectional"))
    )
    (net (code "99") (name "unconnected-(U1-PC4(ADC4{slash}SDA)-Pad27)") (class "Default")
      (node (ref "U1") (pin "27") (pinfunction "PC4(ADC4/SDA)_27") (pintype "bidirectional"))
    )
    (net (code "100") (name "unconnected-(U1-PC5(ADC5{slash}SCL)-Pad28)") (class "Default")
      (node (ref "U1") (pin "28") (pinfunction "PC5(ADC5/SCL)_28") (pintype "bidirectional"))
    )
    (net (code "101") (name "unconnected-(U1-PD2(INT0)-Pad32)") (class "Default")
      (node (ref "U1") (pin "32") (pinfunction "PD2(INT0)_32") (pintype "bidirectional"))
    )
    (net (code "102") (name "unconnected-(U1-PD3(INT1)-Pad1)") (class "Default")
      (node (ref "U1") (pin "1") (pinfunction "PD3(INT1)_1") (pintype "bidirectional"))
    )
    (net (code "103") (name "unconnected-(U1-PD4(XCK{slash}T0)-Pad2)") (class "Default")
      (node (ref "U1") (pin "2") (pinfunction "PD4(XCK/T0)_2") (pintype "bidirectional"))
    )
    (net (code "104") (name "unconnected-(U2-ADC6-Pad19)") (class "Default")
      (node (ref "U2") (pin "19") (pinfunction "ADC6_19") (pintype "bidirectional"))
    )
    (net (code "105") (name "unconnected-(U2-ADC7-Pad22)") (class "Default")
      (node (ref "U2") (pin "22") (pinfunction "ADC7_22") (pintype "bidirectional"))
    )
    (net (code "106") (name "unconnected-(U2-AREF-Pad20)") (class "Default")
      (node (ref "U2") (pin "20") (pinfunction "AREF_20") (pintype "bidirectional"))
    )
    (net (code "107") (name "unconnected-(U2-PC1(ADC1)-Pad24)") (class "Default")
      (node (ref "U2") (pin "24") (pinfunction "PC1(ADC1)_24") (pintype "bidirectional"))
    )
    (net (code "108") (name "unconnected-(U2-PC2(ADC2)-Pad25)") (class "Default")
      (node (ref "U2") (pin "25") (pinfunction "PC2(ADC2)_25") (pintype "bidirectional"))
    )
    (net (code "109") (name "unconnected-(U2-PC3(ADC3)-Pad26)") (class "Default")
      (node (ref "U2") (pin "26") (pinfunction "PC3(ADC3)_26") (pintype "bidirectional"))
    )
    (net (code "110") (name "unconnected-(ULTRA_SISTEM-Pad5)") (class "Default")
      (node (ref "ULTRA_SISTEM") (pin "5") (pinfunction "5_5") (pintype "passive"))
    )
  )
)
